# Sheet1.net
KiCad netlist of a schematic drawn in Altium Designer
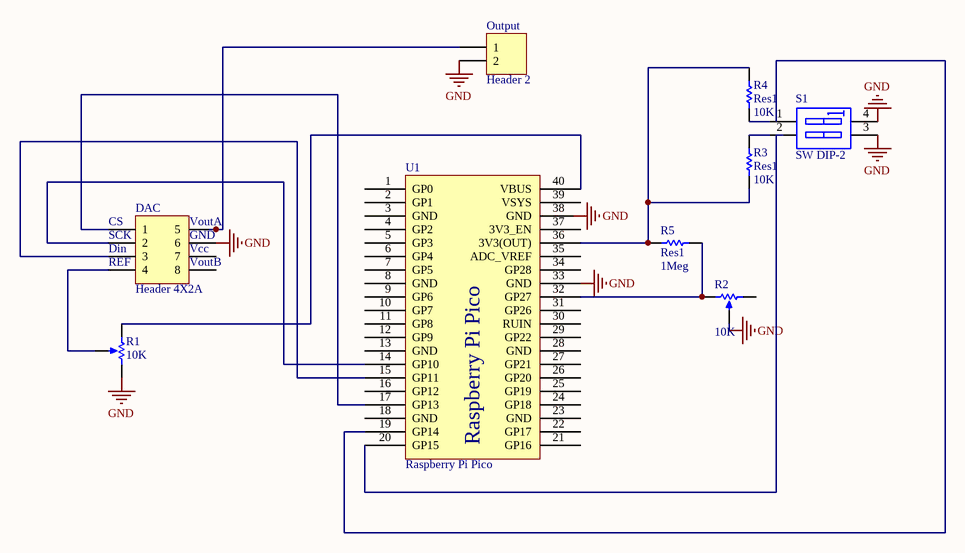
[diagram p0: Sheet1.SchDoc]

(export (version "E")
  (design (tool "Eeschema 10.0.6"))
  (components
    (comp (ref "DAC")
      (value "Header 4X2A")
      (footprint "HDR2X4_CEN")
      (description "Header, 4-Pin, Dual row")
      (fields (field (name "PUBLISHER") "Altium Limited"))
      (libsource (lib "Miscellaneous Connectors") (part "Header 4X2A"))
    )
    (comp (ref "Output")
      (value "Header 2")
      (footprint "HDR1X2")
      (description "Header, 2-Pin")
      (fields (field (name "PUBLISHER") "Altium Limited"))
      (libsource (lib "Miscellaneous Connectors") (part "Header 2"))
    )
    (comp (ref "R1")
      (value "10K")
      (footprint "POT OFFSET 200")
      (description "Potentiometer")
      (fields (field (name "Comment") "RPot_3") (field (name "PUBLISHER") "Altium Limited"))
      (libsource (lib "ECE Lib 22") (part "RPot"))
    )
    (comp (ref "R2")
      (value "10K")
      (footprint "POT OFFSET 200")
      (description "Potentiometer")
      (fields (field (name "Comment") "RPot_3") (field (name "PUBLISHER") "Altium Limited"))
      (libsource (lib "ECE Lib 22") (part "RPot"))
    )
    (comp (ref "R3")
      (value "Res1")
      (footprint "AXIAL-0.3")
      (description "Resistor")
      (fields (field (name "ALTIUM_VALUE") "10K") (field (name "PUBLISHER") "Altium Limited"))
      (libsource (lib "Miscellaneous Devices") (part "Res1"))
    )
    (comp (ref "R4")
      (value "Res1")
      (footprint "AXIAL-0.3")
      (description "Resistor")
      (fields (field (name "ALTIUM_VALUE") "10K") (field (name "PUBLISHER") "Altium Limited"))
      (libsource (lib "Miscellaneous Devices") (part "Res1"))
    )
    (comp (ref "R5")
      (value "Res1")
      (footprint "AXIAL-0.3")
      (description "Resistor")
      (fields (field (name "ALTIUM_VALUE") "1Meg") (field (name "PUBLISHER") "Altium Limited"))
      (libsource (lib "Miscellaneous Devices") (part "Res1"))
    )
    (comp (ref "S1")
      (value "SW DIP-2")
      (footprint "DIP-4")
      (description "DIP Switch, 2 Position, SPST")
      (fields (field (name "PUBLISHER") "Altium Limited"))
      (libsource (lib "Miscellaneous Devices") (part "SW DIP-2"))
    )
    (comp (ref "U1")
      (value "Raspberry Pi Pico")
      (footprint "Raspberry Pi Pico")
      (libsource (lib "ECE Lib 22") (part "Raspberry Pi Pico"))
    )
  )
  (nets
    (net (code "1") (name "GND") (class "Default")
      (node (ref "DAC") (pin "6") (pinfunction "6_6") (pintype "passive"))
      (node (ref "Output") (pin "2") (pinfunction "2_2") (pintype "passive"))
      (node (ref "R1") (pin "3") (pinfunction "BOT_3") (pintype "passive"))
      (node (ref "R2") (pin "2") (pinfunction "TAP_2") (pintype "passive"))
      (node (ref "S1") (pin "3") (pinfunction "B2_3") (pintype "passive"))
      (node (ref "S1") (pin "4") (pinfunction "B1_4") (pintype "passive"))
      (node (ref "U1") (pin "33") (pinfunction "GND_33") (pintype "passive"))
    )
    (net (code "2") (name "Net-(DAC-Pad5)") (class "Default")
      (node (ref "DAC") (pin "5") (pinfunction "5_5") (pintype "passive"))
      (node (ref "Output") (pin "1") (pinfunction "1_1") (pintype "passive"))
    )
    (net (code "3") (name "Net-(R1-TAP)") (class "Default")
      (node (ref "DAC") (pin "4") (pinfunction "4_4") (pintype "passive"))
      (node (ref "R1") (pin "2") (pinfunction "TAP_2") (pintype "passive"))
    )
    (net (code "4") (name "Net-(R1-TOP)") (class "Default")
      (node (ref "R1") (pin "1") (pinfunction "TOP_1") (pintype "passive"))
      (node (ref "U1") (pin "40") (pinfunction "VBUS_40") (pintype "passive"))
    )
    (net (code "5") (name "Net-(R2-TOP)") (class "Default")
      (node (ref "R2") (pin "1") (pinfunction "TOP_1") (pintype "passive"))
      (node (ref "R5") (pin "2") (pinfunction "2_2") (pintype "passive"))
      (node (ref "U1") (pin "32") (pinfunction "GP27_32") (pintype "passive"))
    )
    (net (code "6") (name "Net-(S1-A1)") (class "Default")
      (node (ref "R4") (pin "2") (pinfunction "2_2") (pintype "passive"))
      (node (ref "S1") (pin "1") (pinfunction "A1_1") (pintype "passive"))
    )
    (net (code "7") (name "Net-(S1-A2)") (class "Default")
      (node (ref "R3") (pin "1") (pinfunction "1_1") (pintype "passive"))
      (node (ref "S1") (pin "2") (pinfunction "A2_2") (pintype "passive"))
    )
    (net (code "8") (name "Net-(U1-3V3(OUT))") (class "Default")
      (node (ref "R3") (pin "2") (pinfunction "2_2") (pintype "passive"))
      (node (ref "R4") (pin "1") (pinfunction "1_1") (pintype "passive"))
      (node (ref "R5") (pin "1") (pinfunction "1_1") (pintype "passive"))
      (node (ref "U1") (pin "36") (pinfunction "3V3(OUT)_36") (pintype "passive"))
    )
    (net (code "9") (name "Net-(U1-GP10)") (class "Default")
      (node (ref "DAC") (pin "2") (pinfunction "2_2") (pintype "passive"))
      (node (ref "U1") (pin "14") (pinfunction "GP10_14") (pintype "passive"))
    )
    (net (code "10") (name "Net-(U1-GP11)") (class "Default")
      (node (ref "DAC") (pin "3") (pinfunction "3_3") (pintype "passive"))
      (node (ref "U1") (pin "15") (pinfunction "GP11_15") (pintype "passive"))
    )
    (net (code "11") (name "Net-(U1-GP13)") (class "Default")
      (node (ref "DAC") (pin "1") (pinfunction "1_1") (pintype "passive"))
      (node (ref "U1") (pin "17") (pinfunction "GP13_17") (pintype "passive"))
    )
    (net (code "12") (name "unconnected-(DAC-Pad7)") (class "Default")
      (node (ref "DAC") (pin "7") (pinfunction "7_7") (pintype "passive"))
    )
    (net (code "13") (name "unconnected-(DAC-Pad8)") (class "Default")
      (node (ref "DAC") (pin "8") (pinfunction "8_8") (pintype "passive"))
    )
    (net (code "14") (name "unconnected-(R2-BOT-Pad3)") (class "Default")
      (node (ref "R2") (pin "3") (pinfunction "BOT_3") (pintype "passive"))
    )
    (net (code "15") (name "unconnected-(U1-3V3_EN-Pad37)") (class "Default")
      (node (ref "U1") (pin "37") (pinfunction "3V3_EN_37") (pintype "passive"))
    )
    (net (code "16") (name "unconnected-(U1-ADC_VREF-Pad35)") (class "Default")
      (node (ref "U1") (pin "35") (pinfunction "ADC_VREF_35") (pintype "passive"))
    )
    (net (code "17") (name "unconnected-(U1-GND-Pad3)") (class "Default")
      (node (ref "U1") (pin "3") (pinfunction "GND_3") (pintype "passive"))
    )
    (net (code "18") (name "unconnected-(U1-GND-Pad8)") (class "Default")
      (node (ref "U1") (pin "8") (pinfunction "GND_8") (pintype "passive"))
    )
    (net (code "19") (name "unconnected-(U1-GND-Pad13)") (class "Default")
      (node (ref "U1") (pin "13") (pinfunction "GND_13") (pintype "passive"))
    )
    (net (code "20") (name "unconnected-(U1-GND-Pad18)") (class "Default")
      (node (ref "U1") (pin "18") (pinfunction "GND_18") (pintype "passive"))
    )
    (net (code "21") (name "unconnected-(U1-GND-Pad23)") (class "Default")
      (node (ref "U1") (pin "23") (pinfunction "GND_23") (pintype "passive"))
    )
    (net (code "22") (name "unconnected-(U1-GND-Pad28)") (class "Default")
      (node (ref "U1") (pin "28") (pinfunction "GND_28") (pintype "passive"))
    )
    (net (code "23") (name "unconnected-(U1-GND-Pad38)") (class "Default")
      (node (ref "U1") (pin "38") (pinfunction "GND_38") (pintype "passive"))
    )
    (net (code "24") (name "unconnected-(U1-GP0-Pad1)") (class "Default")
      (node (ref "U1") (pin "1") (pinfunction "GP0_1") (pintype "passive"))
    )
    (net (code "25") (name "unconnected-(U1-GP1-Pad2)") (class "Default")
      (node (ref "U1") (pin "2") (pinfunction "GP1_2") (pintype "passive"))
    )
    (net (code "26") (name "unconnected-(U1-GP2-Pad4)") (class "Default")
      (node (ref "U1") (pin "4") (pinfunction "GP2_4") (pintype "passive"))
    )
    (net (code "27") (name "unconnected-(U1-GP3-Pad5)") (class "Default")
      (node (ref "U1") (pin "5") (pinfunction "GP3_5") (pintype "passive"))
    )
    (net (code "28") (name "unconnected-(U1-GP4-Pad6)") (class "Default")
      (node (ref "U1") (pin "6") (pinfunction "GP4_6") (pintype "passive"))
    )
    (net (code "29") (name "unconnected-(U1-GP5-Pad7)") (class "Default")
      (node (ref "U1") (pin "7") (pinfunction "GP5_7") (pintype "passive"))
    )
    (net (code "30") (name "unconnected-(U1-GP6-Pad9)") (class "Default")
      (node (ref "U1") (pin "9") (pinfunction "GP6_9") (pintype "passive"))
    )
    (net (code "31") (name "unconnected-(U1-GP7-Pad10)") (class "Default")
      (node (ref "U1") (pin "10") (pinfunction "GP7_10") (pintype "passive"))
    )
    (net (code "32") (name "unconnected-(U1-GP8-Pad11)") (class "Default")
      (node (ref "U1") (pin "11") (pinfunction "GP8_11") (pintype "passive"))
    )
    (net (code "33") (name "unconnected-(U1-GP9-Pad12)") (class "Default")
      (node (ref "U1") (pin "12") (pinfunction "GP9_12") (pintype "passive"))
    )
    (net (code "34") (name "unconnected-(U1-GP12-Pad16)") (class "Default")
      (node (ref "U1") (pin "16") (pinfunction "GP12_16") (pintype "passive"))
    )
    (net (code "35") (name "unconnected-(U1-GP14-Pad19)") (class "Default")
      (node (ref "U1") (pin "19") (pinfunction "GP14_19") (pintype "passive"))
    )
    (net (code "36") (name "unconnected-(U1-GP15-Pad20)") (class "Default")
      (node (ref "U1") (pin "20") (pinfunction "GP15_20") (pintype "passive"))
    )
    (net (code "37") (name "unconnected-(U1-GP16-Pad21)") (class "Default")
      (node (ref "U1") (pin "21") (pinfunction "GP16_21") (pintype "passive"))
    )
    (net (code "38") (name "unconnected-(U1-GP17-Pad22)") (class "Default")
      (node (ref "U1") (pin "22") (pinfunction "GP17_22") (pintype "passive"))
    )
    (net (code "39") (name "unconnected-(U1-GP18-Pad24)") (class "Default")
      (node (ref "U1") (pin "24") (pinfunction "GP18_24") (pintype "passive"))
    )
    (net (code "40") (name "unconnected-(U1-GP19-Pad25)") (class "Default")
      (node (ref "U1") (pin "25") (pinfunction "GP19_25") (pintype "passive"))
    )
    (net (code "41") (name "unconnected-(U1-GP20-Pad26)") (class "Default")
      (node (ref "U1") (pin "26") (pinfunction "GP20_26") (pintype "passive"))
    )
    (net (code "42") (name "unconnected-(U1-GP21-Pad27)") (class "Default")
      (node (ref "U1") (pin "27") (pinfunction "GP21_27") (pintype "passive"))
    )
    (net (code "43") (name "unconnected-(U1-GP22-Pad29)") (class "Default")
      (node (ref "U1") (pin "29") (pinfunction "GP22_29") (pintype "passive"))
    )
    (net (code "44") (name "unconnected-(U1-GP26-Pad31)") (class "Default")
      (node (ref "U1") (pin "31") (pinfunction "GP26_31") (pintype "passive"))
    )
    (net (code "45") (name "unconnected-(U1-GP28-Pad34)") (class "Default")
      (node (ref "U1") (pin "34") (pinfunction "GP28_34") (pintype "passive"))
    )
    (net (code "46") (name "unconnected-(U1-RUIN-Pad30)") (class "Default")
      (node (ref "U1") (pin "30") (pinfunction "RUIN_30") (pintype "passive"))
    )
    (net (code "47") (name "unconnected-(U1-VSYS-Pad39)") (class "Default")
      (node (ref "U1") (pin "39") (pinfunction "VSYS_39") (pintype "passive"))
    )
  )
)
